# F_V1__CommMunication_Sheet.net
KiCad netlist of a schematic drawn in Altium Designer
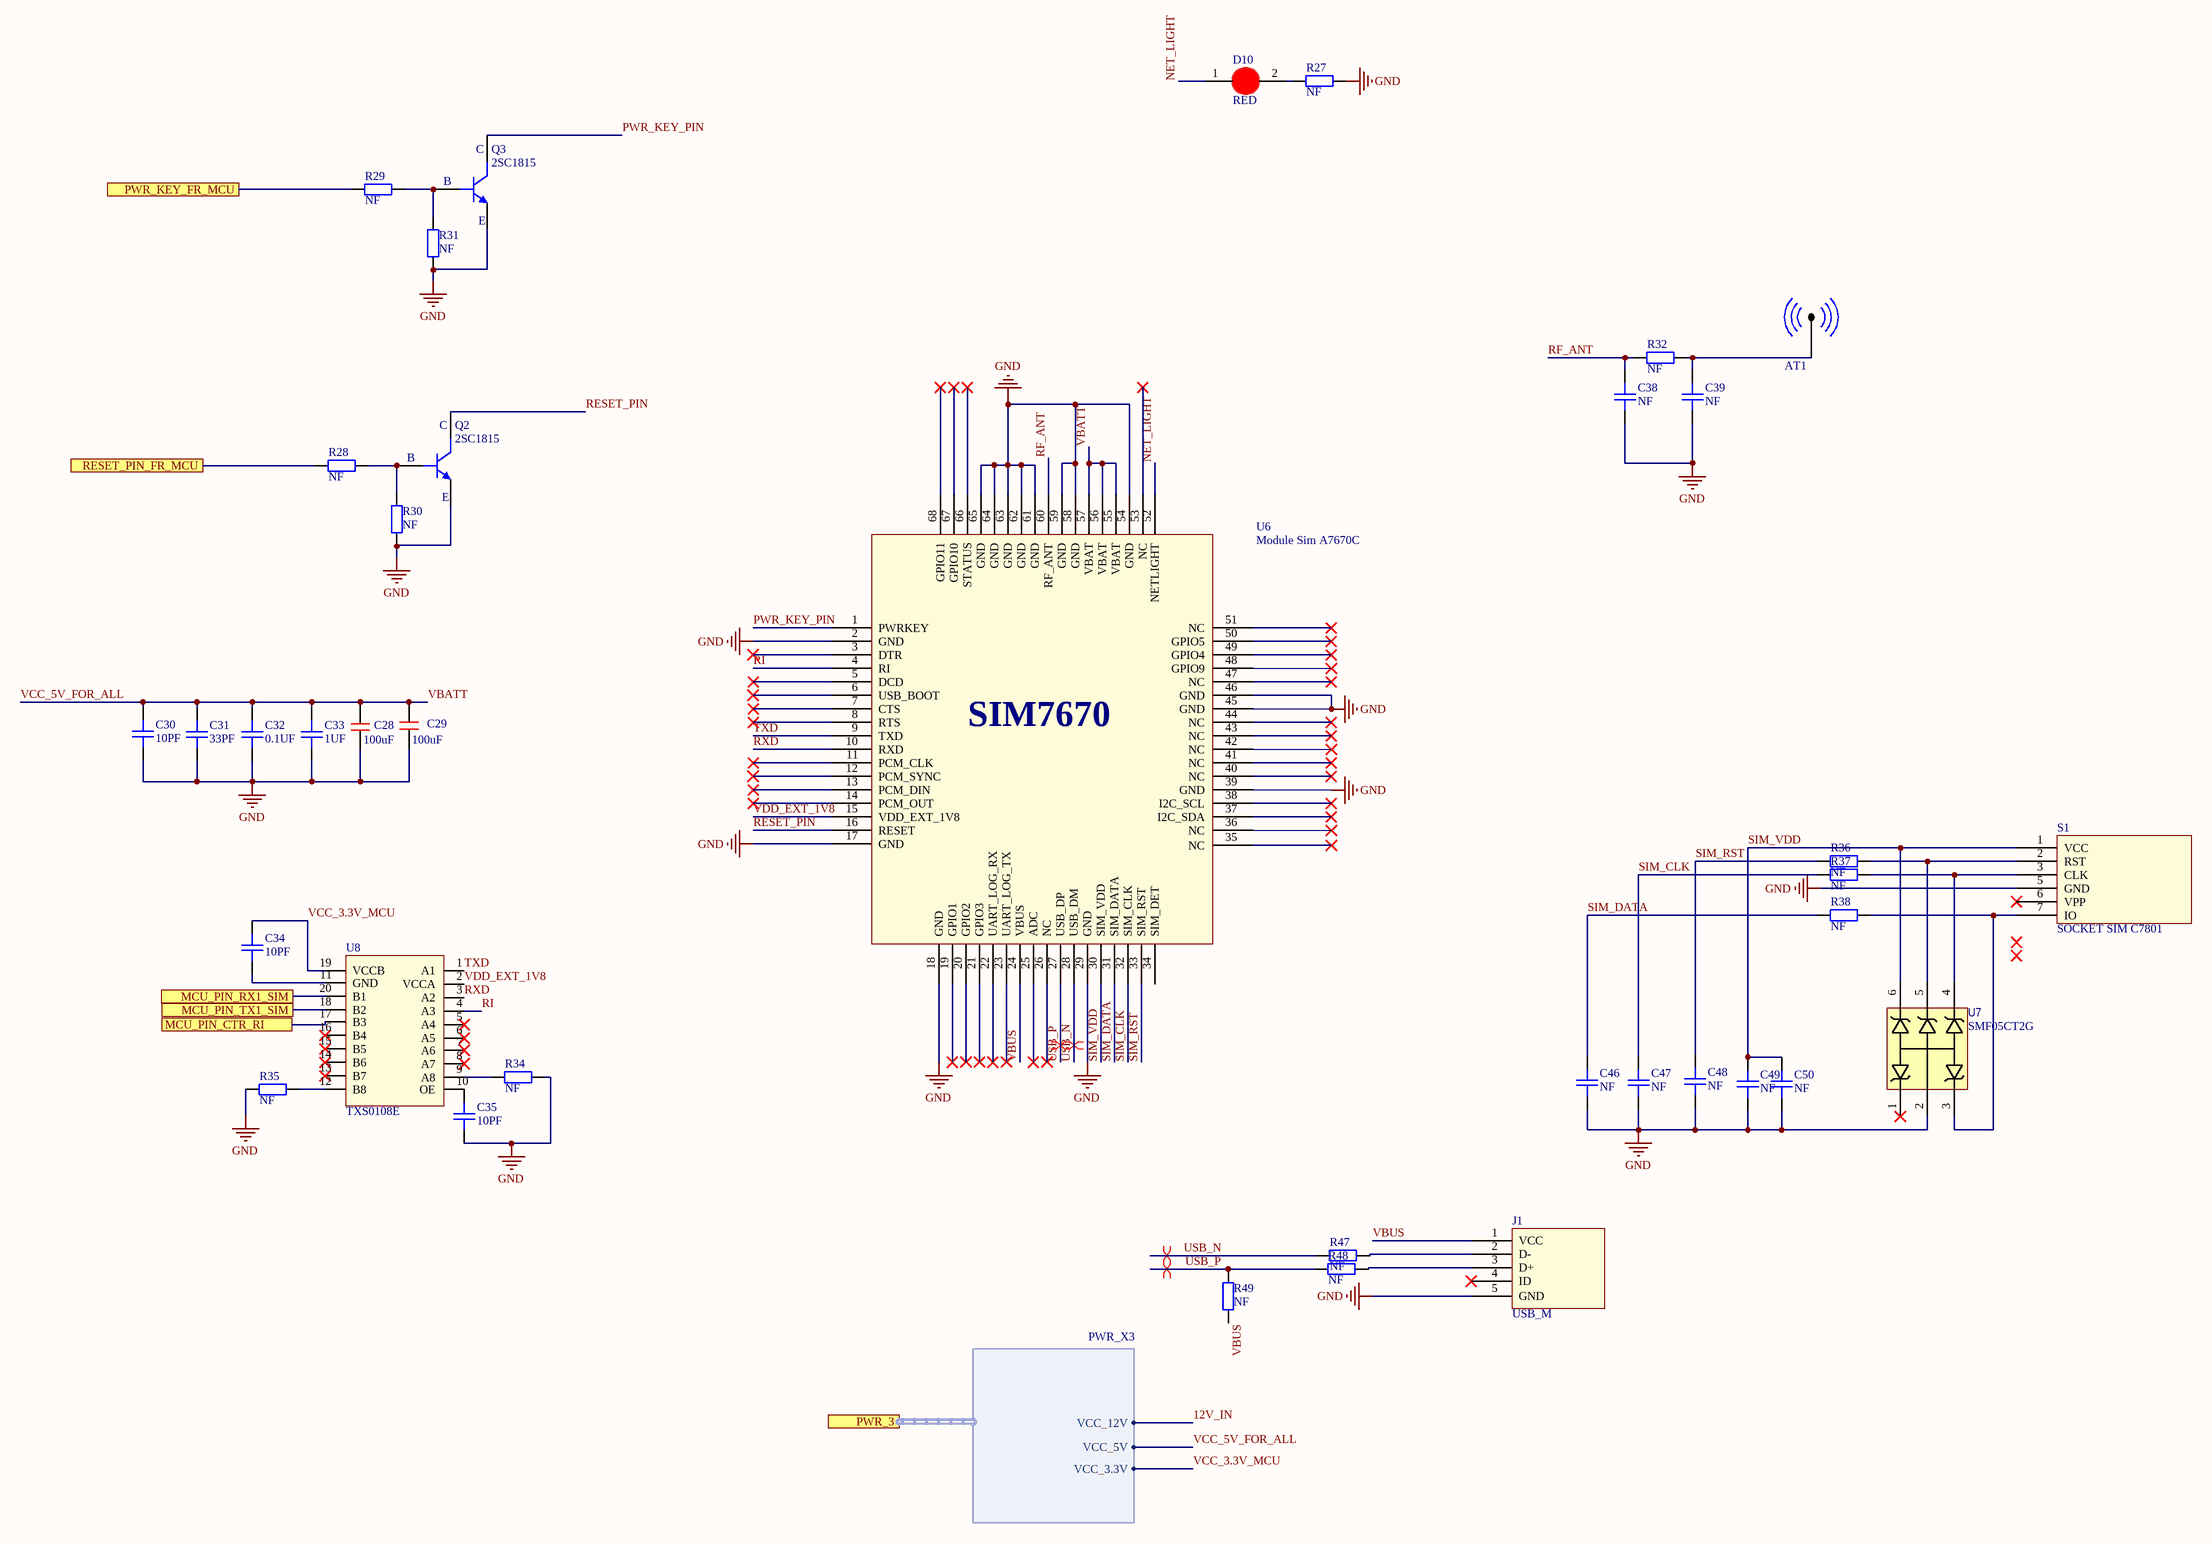
[diagram p0: [F_V1]_CommMunication_Sheet.SchDoc]

(export (version "E")
  (design (tool "Eeschema 10.0.6"))
  (components
    (comp (ref "AT1")
      (value "AT-GSM-GPS")
      (footprint "ANTENA - SMA2")
      (description "CONNECTER ANTENNA GPS GSM")
      (fields (field (name "MPN") "RFCON171003SF6B001"))
      (libsource (lib "BYTECH_HW_LIB_2019") (part "RFCON171003SF6B001"))
    )
    (comp (ref "C28")
      (value "100uF")
      (footprint "100uF 1210 SMD")
      (libsource (lib "FM_Components") (part "CAP SMD 1210 100uF"))
    )
    (comp (ref "C29")
      (value "100uF")
      (footprint "100uF 1210 SMD")
      (libsource (lib "FM_Components") (part "CAP SMD 1210 100uF"))
    )
    (comp (ref "C30")
      (value "10PF")
      (footprint "CAPC-0603 (1608)")
      (description "CAP SMD, Not Fill, 0603")
      (libsource (lib "BYTECH_HW_LIB_2019") (part "CAPC NF 0603"))
    )
    (comp (ref "C31")
      (value "33PF")
      (footprint "CAPC-0603 (1608)")
      (description "CAP SMD, Not Fill, 0603")
      (libsource (lib "BYTECH_HW_LIB_2019") (part "CAPC NF 0603"))
    )
    (comp (ref "C32")
      (value "0.1UF")
      (footprint "CAPC-0603 (1608)")
      (description "CAP SMD, Not Fill, 0603")
      (libsource (lib "BYTECH_HW_LIB_2019") (part "CAPC NF 0603"))
    )
    (comp (ref "C33")
      (value "1UF")
      (footprint "CAPC-0603 (1608)")
      (description "CAP SMD, Not Fill, 0603")
      (libsource (lib "BYTECH_HW_LIB_2019") (part "CAPC NF 0603"))
    )
    (comp (ref "C34")
      (value "10PF")
      (footprint "CAPC-0603 (1608)")
      (description "CAP SMD, Not Fill, 0603")
      (libsource (lib "BYTECH_HW_LIB_2019") (part "CAPC NF 0603"))
    )
    (comp (ref "C35")
      (value "10PF")
      (footprint "CAPC-0603 (1608)")
      (description "CAP SMD, Not Fill, 0603")
      (libsource (lib "BYTECH_HW_LIB_2019") (part "CAPC NF 0603"))
    )
    (comp (ref "C38")
      (value "NF")
      (footprint "CAPC-0603 (1608)")
      (description "CAP SMD, Not Fill, 0603")
      (libsource (lib "BYTECH_HW_LIB_2019") (part "CAPC NF 0603"))
    )
    (comp (ref "C39")
      (value "NF")
      (footprint "CAPC-0603 (1608)")
      (description "CAP SMD, Not Fill, 0603")
      (libsource (lib "BYTECH_HW_LIB_2019") (part "CAPC NF 0603"))
    )
    (comp (ref "C46")
      (value "NF")
      (footprint "CAPC-0603 (1608)")
      (description "CAP SMD, Not Fill, 0603")
      (libsource (lib "BYTECH_HW_LIB_2019") (part "CAPC NF 0603"))
    )
    (comp (ref "C47")
      (value "NF")
      (footprint "CAPC-0603 (1608)")
      (description "CAP SMD, Not Fill, 0603")
      (libsource (lib "BYTECH_HW_LIB_2019") (part "CAPC NF 0603"))
    )
    (comp (ref "C48")
      (value "NF")
      (footprint "CAPC-0603 (1608)")
      (description "CAP SMD, Not Fill, 0603")
      (libsource (lib "BYTECH_HW_LIB_2019") (part "CAPC NF 0603"))
    )
    (comp (ref "C49")
      (value "NF")
      (footprint "CAPC-0603 (1608)")
      (description "CAP SMD, Not Fill, 0603")
      (libsource (lib "BYTECH_HW_LIB_2019") (part "CAPC NF 0603"))
    )
    (comp (ref "C50")
      (value "NF")
      (footprint "CAPC-0603 (1608)")
      (description "CAP SMD, Not Fill, 0603")
      (libsource (lib "BYTECH_HW_LIB_2019") (part "CAPC NF 0603"))
    )
    (comp (ref "D10")
      (value "RED")
      (footprint "LED_0603_RED")
      (description "LED RED 0603 SMD")
      (libsource (lib "BYTECH_HW_LIB_2019") (part "LED RED 0603"))
    )
    (comp (ref "J1") (value "USB_M") (footprint "USB_M") (libsource (lib "FM_Components") (part "USB_M")))
    (comp (ref "Q2")
      (value "2SC1815")
      (footprint "SOT23_3")
      (description "TRANS NPN 50V 0.15A SOT23-3")
      (libsource (lib "BYTECH_HW_LIB_2019") (part "2SC1815"))
    )
    (comp (ref "Q3")
      (value "2SC1815")
      (footprint "SOT23_3")
      (description "TRANS NPN 50V 0.15A SOT23-3")
      (libsource (lib "BYTECH_HW_LIB_2019") (part "2SC1815"))
    )
    (comp (ref "R27")
      (value "NF")
      (footprint "RESC-0603 (1608)")
      (description "RES SMD, Not Fill, 0603")
      (libsource (lib "BYTECH_HW_LIB_2019") (part "RESC NF 0603"))
    )
    (comp (ref "R28")
      (value "NF")
      (footprint "RESC-0603 (1608)")
      (description "RES SMD, Not Fill, 0603")
      (libsource (lib "BYTECH_HW_LIB_2019") (part "RESC NF 0603"))
    )
    (comp (ref "R29")
      (value "NF")
      (footprint "RESC-0603 (1608)")
      (description "RES SMD, Not Fill, 0603")
      (libsource (lib "BYTECH_HW_LIB_2019") (part "RESC NF 0603"))
    )
    (comp (ref "R30")
      (value "NF")
      (footprint "RESC-0603 (1608)")
      (description "RES SMD, Not Fill, 0603")
      (libsource (lib "") (part "RESC NF 0603_1"))
    )
    (comp (ref "R31")
      (value "NF")
      (footprint "RESC-0603 (1608)")
      (description "RES SMD, Not Fill, 0603")
      (libsource (lib "") (part "RESC NF 0603_1"))
    )
    (comp (ref "R32")
      (value "NF")
      (footprint "RESC-0603 (1608)")
      (description "RES SMD, Not Fill, 0603")
      (libsource (lib "BYTECH_HW_LIB_2019") (part "RESC NF 0603"))
    )
    (comp (ref "R34")
      (value "NF")
      (footprint "RESC-0603 (1608)")
      (description "RES SMD, Not Fill, 0603")
      (libsource (lib "BYTECH_HW_LIB_2019") (part "RESC NF 0603"))
    )
    (comp (ref "R35")
      (value "NF")
      (footprint "RESC-0603 (1608)")
      (description "RES SMD, Not Fill, 0603")
      (libsource (lib "BYTECH_HW_LIB_2019") (part "RESC NF 0603"))
    )
    (comp (ref "R36")
      (value "NF")
      (footprint "RESC-0603 (1608)")
      (description "RES SMD, Not Fill, 0603")
      (libsource (lib "BYTECH_HW_LIB_2019") (part "RESC NF 0603"))
    )
    (comp (ref "R37")
      (value "NF")
      (footprint "RESC-0603 (1608)")
      (description "RES SMD, Not Fill, 0603")
      (libsource (lib "BYTECH_HW_LIB_2019") (part "RESC NF 0603"))
    )
    (comp (ref "R38")
      (value "NF")
      (footprint "RESC-0603 (1608)")
      (description "RES SMD, Not Fill, 0603")
      (libsource (lib "BYTECH_HW_LIB_2019") (part "RESC NF 0603"))
    )
    (comp (ref "R47")
      (value "NF")
      (footprint "RESC-0603 (1608)")
      (description "RES SMD, Not Fill, 0603")
      (libsource (lib "BYTECH_HW_LIB_2019") (part "RESC NF 0603"))
    )
    (comp (ref "R48")
      (value "NF")
      (footprint "RESC-0603 (1608)")
      (description "RES SMD, Not Fill, 0603")
      (libsource (lib "BYTECH_HW_LIB_2019") (part "RESC NF 0603"))
    )
    (comp (ref "R49")
      (value "NF")
      (footprint "RESC-0603 (1608)")
      (description "RES SMD, Not Fill, 0603")
      (libsource (lib "") (part "RESC NF 0603_1"))
    )
    (comp (ref "S1")
      (value "SOCKET SIM C7801")
      (footprint "SOCKET SIM")
      (libsource (lib "FM_Components") (part "SOCKET SIM C7801"))
    )
    (comp (ref "U6")
      (value "Module Sim A7670C")
      (footprint "Module Sim A7670C")
      (libsource (lib "FM_Components") (part "Module Sim A7670C"))
    )
    (comp (ref "U7")
      (value "SMF05CT2G")
      (footprint "SOT65P210X140-6N")
      (description "TVS Diode Array For ESD and Latch-Up Protection")
      (fields (field (name "MFR") "ON SEMICONDUCTOR"))
      (libsource (lib "BYTECH_HW_LIB_2019") (part "SMF05C"))
    )
    (comp (ref "U8")
      (value "TXS0108E")
      (footprint "TXS0108E")
      (libsource (lib "FM_Components") (part "TXS0108E"))
    )
  )
  (nets
    (net (code "3") (name "/MCU_PIN_CTR_RI") (class "Default")
      (node (ref "U8") (pin "17") (pinfunction "B3_17") (pintype "passive"))
    )
    (net (code "4") (name "/MCU_PIN_RX1_SIM") (class "Default")
      (node (ref "U8") (pin "20") (pinfunction "B1_20") (pintype "passive"))
    )
    (net (code "5") (name "/MCU_PIN_TX1_SIM") (class "Default")
      (node (ref "U8") (pin "18") (pinfunction "B2_18") (pintype "passive"))
    )
    (net (code "6") (name "/NET_LIGHT") (class "Default")
      (node (ref "D10") (pin "1") (pinfunction "A_1") (pintype "passive"))
      (node (ref "U6") (pin "52") (pinfunction "NETLIGHT_52") (pintype "passive"))
    )
    (net (code "7") (name "/PWR_KEY_FR_MCU") (class "Default")
      (node (ref "R29") (pin "2") (pinfunction "2_2") (pintype "passive"))
    )
    (net (code "8") (name "/PWR_KEY_PIN") (class "Default")
      (node (ref "Q3") (pin "3") (pinfunction "C_3") (pintype "passive"))
      (node (ref "U6") (pin "1") (pinfunction "PWRKEY_1") (pintype "passive"))
    )
    (net (code "9") (name "/RESET_PIN") (class "Default")
      (node (ref "Q2") (pin "3") (pinfunction "C_3") (pintype "passive"))
      (node (ref "U6") (pin "16") (pinfunction "RESET_16") (pintype "passive"))
    )
    (net (code "10") (name "/RESET_PIN_FR_MCU") (class "Default")
      (node (ref "R28") (pin "2") (pinfunction "2_2") (pintype "passive"))
    )
    (net (code "11") (name "/RF_ANT") (class "Default")
      (node (ref "C38") (pin "2") (pinfunction "2_2") (pintype "passive"))
      (node (ref "R32") (pin "2") (pinfunction "2_2") (pintype "passive"))
      (node (ref "U6") (pin "60") (pinfunction "RF_ANT_60") (pintype "passive"))
    )
    (net (code "12") (name "/RI") (class "Default")
      (node (ref "U6") (pin "4") (pinfunction "RI_4") (pintype "passive"))
      (node (ref "U8") (pin "4") (pinfunction "A3_4") (pintype "passive"))
    )
    (net (code "13") (name "/RXD") (class "Default")
      (node (ref "U6") (pin "10") (pinfunction "RXD_10") (pintype "passive"))
      (node (ref "U8") (pin "3") (pinfunction "A2_3") (pintype "passive"))
    )
    (net (code "14") (name "/SIM_CLK") (class "Default")
      (node (ref "C47") (pin "2") (pinfunction "2_2") (pintype "passive"))
      (node (ref "R37") (pin "2") (pinfunction "2_2") (pintype "passive"))
      (node (ref "U6") (pin "32") (pinfunction "SIM_CLK_32") (pintype "passive"))
    )
    (net (code "15") (name "/SIM_DATA") (class "Default")
      (node (ref "C46") (pin "2") (pinfunction "2_2") (pintype "passive"))
      (node (ref "R38") (pin "2") (pinfunction "2_2") (pintype "passive"))
      (node (ref "U6") (pin "31") (pinfunction "SIM_DATA_31") (pintype "passive"))
    )
    (net (code "16") (name "/SIM_RST") (class "Default")
      (node (ref "C48") (pin "2") (pinfunction "2_2") (pintype "passive"))
      (node (ref "R36") (pin "2") (pinfunction "2_2") (pintype "passive"))
      (node (ref "U6") (pin "33") (pinfunction "SIM_RST_33") (pintype "passive"))
    )
    (net (code "17") (name "/SIM_VDD") (class "Default")
      (node (ref "C49") (pin "2") (pinfunction "2_2") (pintype "passive"))
      (node (ref "C50") (pin "2") (pinfunction "2_2") (pintype "passive"))
      (node (ref "S1") (pin "1") (pinfunction "VCC_1") (pintype "passive"))
      (node (ref "U6") (pin "30") (pinfunction "SIM_VDD_30") (pintype "passive"))
      (node (ref "U7") (pin "6") (pinfunction "CT5_6") (pintype "passive"))
    )
    (net (code "18") (name "/TXD") (class "Default")
      (node (ref "U6") (pin "9") (pinfunction "TXD_9") (pintype "passive"))
      (node (ref "U8") (pin "1") (pinfunction "A1_1") (pintype "passive"))
    )
    (net (code "19") (name "/USB_N") (class "Default")
      (node (ref "R47") (pin "2") (pinfunction "2_2") (pintype "passive"))
      (node (ref "U6") (pin "28") (pinfunction "USB_DM_28") (pintype "passive"))
    )
    (net (code "20") (name "/USB_P") (class "Default")
      (node (ref "R48") (pin "2") (pinfunction "2_2") (pintype "passive"))
      (node (ref "R49") (pin "1") (pinfunction "1_1") (pintype "passive"))
      (node (ref "U6") (pin "27") (pinfunction "USB_DP_27") (pintype "passive"))
    )
    (net (code "21") (name "/VBATT") (class "Default")
      (node (ref "C28") (pin "2") (pinfunction "2_2") (pintype "passive"))
      (node (ref "C29") (pin "2") (pinfunction "2_2") (pintype "passive"))
      (node (ref "C30") (pin "2") (pinfunction "2_2") (pintype "passive"))
      (node (ref "C31") (pin "2") (pinfunction "2_2") (pintype "passive"))
      (node (ref "C32") (pin "2") (pinfunction "2_2") (pintype "passive"))
      (node (ref "C33") (pin "2") (pinfunction "2_2") (pintype "passive"))
      (node (ref "U6") (pin "55") (pinfunction "VBAT_55") (pintype "passive"))
      (node (ref "U6") (pin "56") (pinfunction "VBAT_56") (pintype "passive"))
      (node (ref "U6") (pin "57") (pinfunction "VBAT_57") (pintype "passive"))
    )
    (net (code "22") (name "/VBUS") (class "Default")
      (node (ref "J1") (pin "1") (pinfunction "VCC_1") (pintype "passive"))
      (node (ref "R49") (pin "2") (pinfunction "2_2") (pintype "passive"))
      (node (ref "U6") (pin "24") (pinfunction "VBUS_24") (pintype "passive"))
    )
    (net (code "23") (name "/VCC_3.3V_MCU") (class "Default")
      (node (ref "C34") (pin "2") (pinfunction "2_2") (pintype "passive"))
      (node (ref "U8") (pin "19") (pinfunction "VCCB_19") (pintype "passive"))
    )
    (net (code "24") (name "/VDD_EXT_1V8") (class "Default")
      (node (ref "U6") (pin "15") (pinfunction "VDD_EXT_1V8_15") (pintype "passive"))
      (node (ref "U8") (pin "2") (pinfunction "VCCA_2") (pintype "passive"))
    )
    (net (code "26") (name "GND") (class "Default")
      (node (ref "C28") (pin "1") (pinfunction "1_1") (pintype "passive"))
      (node (ref "C29") (pin "1") (pinfunction "1_1") (pintype "passive"))
      (node (ref "C30") (pin "1") (pinfunction "1_1") (pintype "passive"))
      (node (ref "C31") (pin "1") (pinfunction "1_1") (pintype "passive"))
      (node (ref "C32") (pin "1") (pinfunction "1_1") (pintype "passive"))
      (node (ref "C33") (pin "1") (pinfunction "1_1") (pintype "passive"))
      (node (ref "C35") (pin "1") (pinfunction "1_1") (pintype "passive"))
      (node (ref "C38") (pin "1") (pinfunction "1_1") (pintype "passive"))
      (node (ref "C39") (pin "1") (pinfunction "1_1") (pintype "passive"))
      (node (ref "C46") (pin "1") (pinfunction "1_1") (pintype "passive"))
      (node (ref "C47") (pin "1") (pinfunction "1_1") (pintype "passive"))
      (node (ref "C48") (pin "1") (pinfunction "1_1") (pintype "passive"))
      (node (ref "C49") (pin "1") (pinfunction "1_1") (pintype "passive"))
      (node (ref "C50") (pin "1") (pinfunction "1_1") (pintype "passive"))
      (node (ref "J1") (pin "5") (pinfunction "GND_5") (pintype "passive"))
      (node (ref "Q2") (pin "2") (pinfunction "E_2") (pintype "passive"))
      (node (ref "Q3") (pin "2") (pinfunction "E_2") (pintype "passive"))
      (node (ref "R27") (pin "1") (pinfunction "1_1") (pintype "passive"))
      (node (ref "R30") (pin "2") (pinfunction "2_2") (pintype "passive"))
      (node (ref "R31") (pin "2") (pinfunction "2_2") (pintype "passive"))
      (node (ref "R34") (pin "1") (pinfunction "1_1") (pintype "passive"))
      (node (ref "R35") (pin "2") (pinfunction "2_2") (pintype "passive"))
      (node (ref "S1") (pin "5") (pinfunction "GND_5") (pintype "passive"))
      (node (ref "U6") (pin "17") (pinfunction "GND_17") (pintype "passive"))
      (node (ref "U6") (pin "18") (pinfunction "GND_18") (pintype "passive"))
      (node (ref "U6") (pin "2") (pinfunction "GND_2") (pintype "passive"))
      (node (ref "U6") (pin "29") (pinfunction "GND_29") (pintype "passive"))
      (node (ref "U6") (pin "39") (pinfunction "GND_39") (pintype "passive"))
      (node (ref "U6") (pin "45") (pinfunction "GND_45") (pintype "passive"))
      (node (ref "U6") (pin "46") (pinfunction "GND_46") (pintype "passive"))
      (node (ref "U6") (pin "54") (pinfunction "GND_54") (pintype "passive"))
      (node (ref "U6") (pin "58") (pinfunction "GND_58") (pintype "passive"))
      (node (ref "U6") (pin "59") (pinfunction "GND_59") (pintype "passive"))
      (node (ref "U6") (pin "61") (pinfunction "GND_61") (pintype "passive"))
      (node (ref "U6") (pin "62") (pinfunction "GND_62") (pintype "passive"))
      (node (ref "U6") (pin "63") (pinfunction "GND_63") (pintype "passive"))
      (node (ref "U6") (pin "64") (pinfunction "GND_64") (pintype "passive"))
      (node (ref "U6") (pin "65") (pinfunction "GND_65") (pintype "passive"))
      (node (ref "U7") (pin "2") (pinfunction "AN_2") (pintype "passive"))
    )
    (net (code "27") (name "Net-(AT1-AT)") (class "Default")
      (node (ref "AT1") (pin "1") (pinfunction "AT_1") (pintype "passive"))
      (node (ref "C39") (pin "2") (pinfunction "2_2") (pintype "passive"))
      (node (ref "R32") (pin "1") (pinfunction "1_1") (pintype "passive"))
    )
    (net (code "28") (name "Net-(D10-K)") (class "Default")
      (node (ref "D10") (pin "2") (pinfunction "K_2") (pintype "passive"))
      (node (ref "R27") (pin "2") (pinfunction "2_2") (pintype "passive"))
    )
    (net (code "29") (name "Net-(J1-D+)") (class "Default")
      (node (ref "J1") (pin "3") (pinfunction "D+_3") (pintype "passive"))
      (node (ref "R48") (pin "1") (pinfunction "1_1") (pintype "passive"))
    )
    (net (code "30") (name "Net-(J1-D-)") (class "Default")
      (node (ref "J1") (pin "2") (pinfunction "D-_2") (pintype "passive"))
      (node (ref "R47") (pin "1") (pinfunction "1_1") (pintype "passive"))
    )
    (net (code "31") (name "Net-(Q2-B)") (class "Default")
      (node (ref "Q2") (pin "1") (pinfunction "B_1") (pintype "passive"))
      (node (ref "R28") (pin "1") (pinfunction "1_1") (pintype "passive"))
      (node (ref "R30") (pin "1") (pinfunction "1_1") (pintype "passive"))
    )
    (net (code "32") (name "Net-(Q3-B)") (class "Default")
      (node (ref "Q3") (pin "1") (pinfunction "B_1") (pintype "passive"))
      (node (ref "R29") (pin "1") (pinfunction "1_1") (pintype "passive"))
      (node (ref "R31") (pin "1") (pinfunction "1_1") (pintype "passive"))
    )
    (net (code "33") (name "Net-(S1-CLK)") (class "Default")
      (node (ref "R37") (pin "1") (pinfunction "1_1") (pintype "passive"))
      (node (ref "S1") (pin "3") (pinfunction "CLK_3") (pintype "passive"))
      (node (ref "U7") (pin "4") (pinfunction "CT3_4") (pintype "passive"))
    )
    (net (code "34") (name "Net-(S1-IO)") (class "Default")
      (node (ref "R38") (pin "1") (pinfunction "1_1") (pintype "passive"))
      (node (ref "S1") (pin "7") (pinfunction "IO_7") (pintype "passive"))
      (node (ref "U7") (pin "3") (pinfunction "CT2_3") (pintype "passive"))
    )
    (net (code "35") (name "Net-(S1-RST)") (class "Default")
      (node (ref "R36") (pin "1") (pinfunction "1_1") (pintype "passive"))
      (node (ref "S1") (pin "2") (pinfunction "RST_2") (pintype "passive"))
      (node (ref "U7") (pin "5") (pinfunction "CT4_5") (pintype "passive"))
    )
    (net (code "36") (name "Net-(U8-A8)") (class "Default")
      (node (ref "R34") (pin "2") (pinfunction "2_2") (pintype "passive"))
      (node (ref "U8") (pin "9") (pinfunction "A8_9") (pintype "passive"))
    )
    (net (code "37") (name "Net-(U8-B8)") (class "Default")
      (node (ref "R35") (pin "1") (pinfunction "1_1") (pintype "passive"))
      (node (ref "U8") (pin "12") (pinfunction "B8_12") (pintype "passive"))
    )
    (net (code "38") (name "Net-(U8-GND)") (class "Default")
      (node (ref "C34") (pin "1") (pinfunction "1_1") (pintype "passive"))
      (node (ref "U8") (pin "11") (pinfunction "GND_11") (pintype "passive"))
    )
    (net (code "39") (name "Net-(U8-OE)") (class "Default")
      (node (ref "C35") (pin "2") (pinfunction "2_2") (pintype "passive"))
      (node (ref "U8") (pin "10") (pinfunction "OE_10") (pintype "passive"))
    )
    (net (code "40") (name "unconnected-(AT1-Pad2)") (class "Default")
      (node (ref "AT1") (pin "2") (pinfunction "2_2") (pintype "passive"))
    )
    (net (code "41") (name "unconnected-(J1-ID-Pad4)") (class "Default")
      (node (ref "J1") (pin "4") (pinfunction "ID_4") (pintype "passive+no_connect"))
    )
    (net (code "42") (name "unconnected-(S1-VPP-Pad6)") (class "Default")
      (node (ref "S1") (pin "6") (pinfunction "VPP_6") (pintype "passive+no_connect"))
    )
    (net (code "43") (name "unconnected-(U6-ADC-Pad25)") (class "Default")
      (node (ref "U6") (pin "25") (pinfunction "ADC_25") (pintype "passive+no_connect"))
    )
    (net (code "44") (name "unconnected-(U6-CTS-Pad7)") (class "Default")
      (node (ref "U6") (pin "7") (pinfunction "CTS_7") (pintype "passive+no_connect"))
    )
    (net (code "45") (name "unconnected-(U6-DCD-Pad5)") (class "Default")
      (node (ref "U6") (pin "5") (pinfunction "DCD_5") (pintype "passive+no_connect"))
    )
    (net (code "46") (name "unconnected-(U6-DTR-Pad3)") (class "Default")
      (node (ref "U6") (pin "3") (pinfunction "DTR_3") (pintype "passive+no_connect"))
    )
    (net (code "47") (name "unconnected-(U6-GPIO1-Pad19)") (class "Default")
      (node (ref "U6") (pin "19") (pinfunction "GPIO1_19") (pintype "passive+no_connect"))
    )
    (net (code "48") (name "unconnected-(U6-GPIO2-Pad20)") (class "Default")
      (node (ref "U6") (pin "20") (pinfunction "GPIO2_20") (pintype "passive+no_connect"))
    )
    (net (code "49") (name "unconnected-(U6-GPIO3-Pad21)") (class "Default")
      (node (ref "U6") (pin "21") (pinfunction "GPIO3_21") (pintype "passive+no_connect"))
    )
    (net (code "50") (name "unconnected-(U6-GPIO4-Pad49)") (class "Default")
      (node (ref "U6") (pin "49") (pinfunction "GPIO4_49") (pintype "passive+no_connect"))
    )
    (net (code "51") (name "unconnected-(U6-GPIO5-Pad50)") (class "Default")
      (node (ref "U6") (pin "50") (pinfunction "GPIO5_50") (pintype "passive+no_connect"))
    )
    (net (code "52") (name "unconnected-(U6-GPIO9-Pad48)") (class "Default")
      (node (ref "U6") (pin "48") (pinfunction "GPIO9_48") (pintype "passive+no_connect"))
    )
    (net (code "53") (name "unconnected-(U6-GPIO10-Pad67)") (class "Default")
      (node (ref "U6") (pin "67") (pinfunction "GPIO10_67") (pintype "passive+no_connect"))
    )
    (net (code "54") (name "unconnected-(U6-GPIO11-Pad68)") (class "Default")
      (node (ref "U6") (pin "68") (pinfunction "GPIO11_68") (pintype "passive+no_connect"))
    )
    (net (code "55") (name "unconnected-(U6-I2C_SCL-Pad38)") (class "Default")
      (node (ref "U6") (pin "38") (pinfunction "I2C_SCL_38") (pintype "passive+no_connect"))
    )
    (net (code "56") (name "unconnected-(U6-I2C_SDA-Pad37)") (class "Default")
      (node (ref "U6") (pin "37") (pinfunction "I2C_SDA_37") (pintype "passive+no_connect"))
    )
    (net (code "57") (name "unconnected-(U6-NC-Pad26)") (class "Default")
      (node (ref "U6") (pin "26") (pinfunction "NC_26") (pintype "passive+no_connect"))
    )
    (net (code "58") (name "unconnected-(U6-NC-Pad35)") (class "Default")
      (node (ref "U6") (pin "35") (pinfunction "NC_35") (pintype "passive+no_connect"))
    )
    (net (code "59") (name "unconnected-(U6-NC-Pad36)") (class "Default")
      (node (ref "U6") (pin "36") (pinfunction "NC_36") (pintype "passive+no_connect"))
    )
    (net (code "60") (name "unconnected-(U6-NC-Pad40)") (class "Default")
      (node (ref "U6") (pin "40") (pinfunction "NC_40") (pintype "passive+no_connect"))
    )
    (net (code "61") (name "unconnected-(U6-NC-Pad41)") (class "Default")
      (node (ref "U6") (pin "41") (pinfunction "NC_41") (pintype "passive+no_connect"))
    )
    (net (code "62") (name "unconnected-(U6-NC-Pad42)") (class "Default")
      (node (ref "U6") (pin "42") (pinfunction "NC_42") (pintype "passive+no_connect"))
    )
    (net (code "63") (name "unconnected-(U6-NC-Pad43)") (class "Default")
      (node (ref "U6") (pin "43") (pinfunction "NC_43") (pintype "passive+no_connect"))
    )
    (net (code "64") (name "unconnected-(U6-NC-Pad44)") (class "Default")
      (node (ref "U6") (pin "44") (pinfunction "NC_44") (pintype "passive+no_connect"))
    )
    (net (code "65") (name "unconnected-(U6-NC-Pad47)") (class "Default")
      (node (ref "U6") (pin "47") (pinfunction "NC_47") (pintype "passive+no_connect"))
    )
    (net (code "66") (name "unconnected-(U6-NC-Pad51)") (class "Default")
      (node (ref "U6") (pin "51") (pinfunction "NC_51") (pintype "passive+no_connect"))
    )
    (net (code "67") (name "unconnected-(U6-NC-Pad53)") (class "Default")
      (node (ref "U6") (pin "53") (pinfunction "NC_53") (pintype "passive+no_connect"))
    )
    (net (code "68") (name "unconnected-(U6-PCM_CLK-Pad11)") (class "Default")
      (node (ref "U6") (pin "11") (pinfunction "PCM_CLK_11") (pintype "passive+no_connect"))
    )
    (net (code "69") (name "unconnected-(U6-PCM_DIN-Pad13)") (class "Default")
      (node (ref "U6") (pin "13") (pinfunction "PCM_DIN_13") (pintype "passive+no_connect"))
    )
    (net (code "70") (name "unconnected-(U6-PCM_OUT-Pad14)") (class "Default")
      (node (ref "U6") (pin "14") (pinfunction "PCM_OUT_14") (pintype "passive+no_connect"))
    )
    (net (code "71") (name "unconnected-(U6-PCM_SYNC-Pad12)") (class "Default")
      (node (ref "U6") (pin "12") (pinfunction "PCM_SYNC_12") (pintype "passive+no_connect"))
    )
    (net (code "72") (name "unconnected-(U6-RTS-Pad8)") (class "Default")
      (node (ref "U6") (pin "8") (pinfunction "RTS_8") (pintype "passive+no_connect"))
    )
    (net (code "73") (name "unconnected-(U6-SIM_DET-Pad34)") (class "Default")
      (node (ref "U6") (pin "34") (pinfunction "SIM_DET_34") (pintype "passive"))
    )
    (net (code "74") (name "unconnected-(U6-STATUS-Pad66)") (class "Default")
      (node (ref "U6") (pin "66") (pinfunction "STATUS_66") (pintype "passive+no_connect"))
    )
    (net (code "75") (name "unconnected-(U6-UART_LOG_RX-Pad22)") (class "Default")
      (node (ref "U6") (pin "22") (pinfunction "UART_LOG_RX_22") (pintype "passive+no_connect"))
    )
    (net (code "76") (name "unconnected-(U6-UART_LOG_TX-Pad23)") (class "Default")
      (node (ref "U6") (pin "23") (pinfunction "UART_LOG_TX_23") (pintype "passive+no_connect"))
    )
    (net (code "77") (name "unconnected-(U6-USB_BOOT-Pad6)") (class "Default")
      (node (ref "U6") (pin "6") (pinfunction "USB_BOOT_6") (pintype "passive+no_connect"))
    )
    (net (code "78") (name "unconnected-(U7-CT1-Pad1)") (class "Default")
      (node (ref "U7") (pin "1") (pinfunction "CT1_1") (pintype "passive+no_connect"))
    )
    (net (code "79") (name "unconnected-(U8-A4-Pad5)") (class "Default")
      (node (ref "U8") (pin "5") (pinfunction "A4_5") (pintype "passive+no_connect"))
    )
    (net (code "80") (name "unconnected-(U8-A5-Pad6)") (class "Default")
      (node (ref "U8") (pin "6") (pinfunction "A5_6") (pintype "passive+no_connect"))
    )
    (net (code "81") (name "unconnected-(U8-A6-Pad7)") (class "Default")
      (node (ref "U8") (pin "7") (pinfunction "A6_7") (pintype "passive+no_connect"))
    )
    (net (code "82") (name "unconnected-(U8-A7-Pad8)") (class "Default")
      (node (ref "U8") (pin "8") (pinfunction "A7_8") (pintype "passive+no_connect"))
    )
    (net (code "83") (name "unconnected-(U8-B4-Pad16)") (class "Default")
      (node (ref "U8") (pin "16") (pinfunction "B4_16") (pintype "passive+no_connect"))
    )
    (net (code "84") (name "unconnected-(U8-B5-Pad15)") (class "Default")
      (node (ref "U8") (pin "15") (pinfunction "B5_15") (pintype "passive+no_connect"))
    )
    (net (code "85") (name "unconnected-(U8-B6-Pad14)") (class "Default")
      (node (ref "U8") (pin "14") (pinfunction "B6_14") (pintype "passive+no_connect"))
    )
    (net (code "86") (name "unconnected-(U8-B7-Pad13)") (class "Default")
      (node (ref "U8") (pin "13") (pinfunction "B7_13") (pintype "passive+no_connect"))
    )
  )
)
